# H05R00.net
KiCad netlist of a schematic drawn in EAGLE
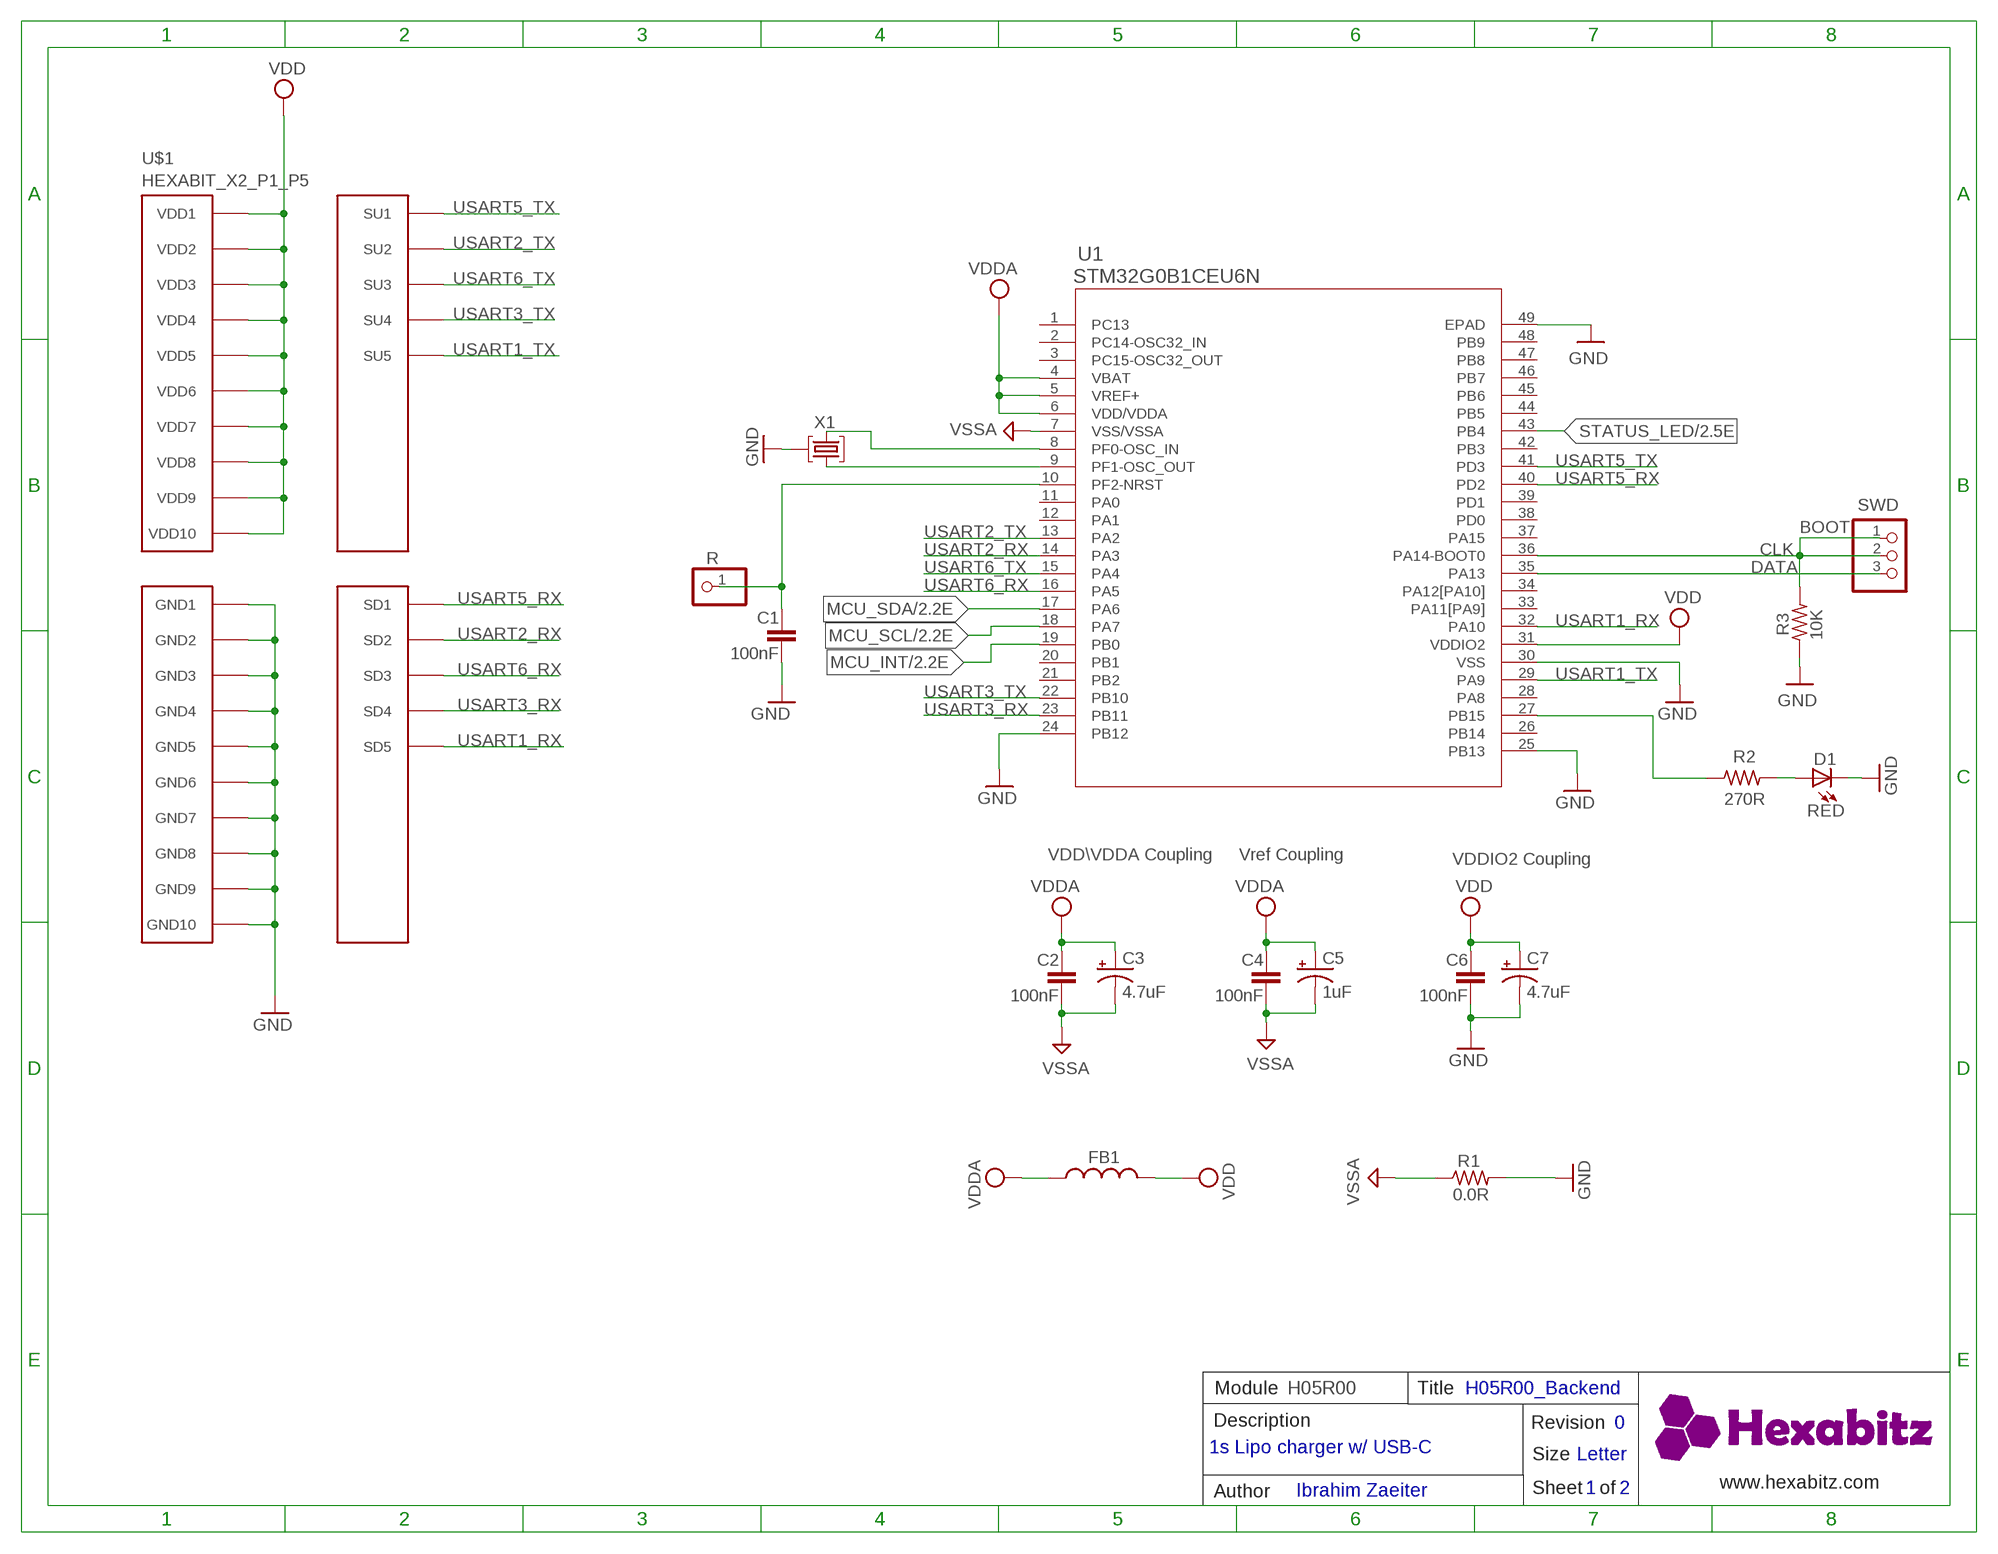
[diagram p0: schematic, sheet 1]
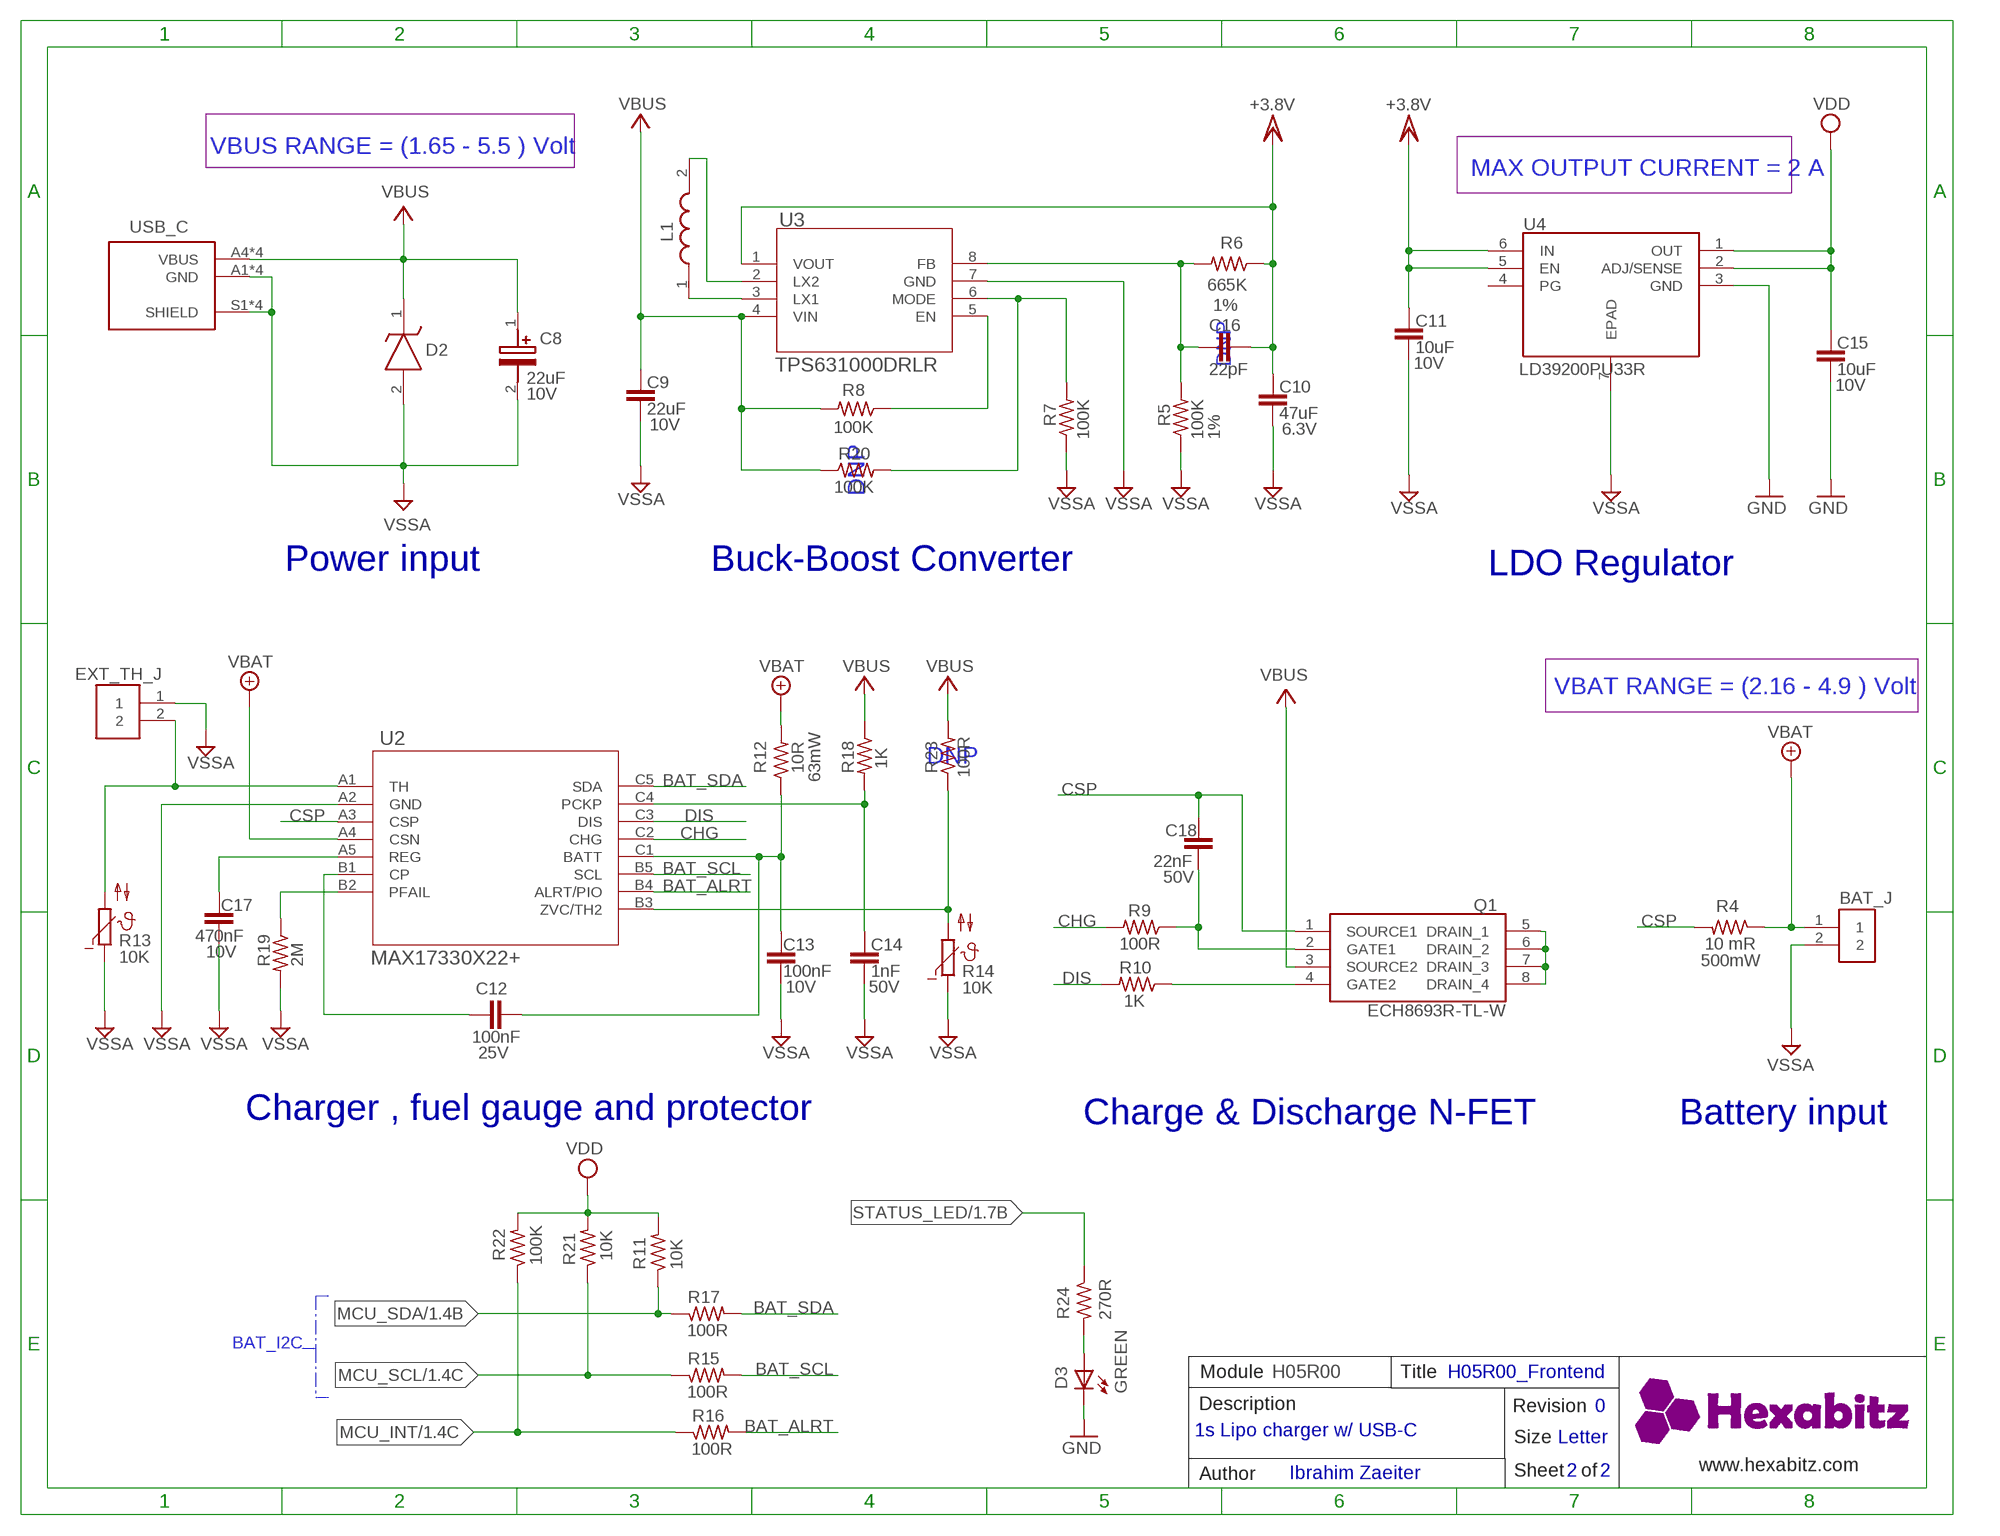
[diagram p1: schematic, sheet 2]

(export (version "E")
  (design (tool "Eeschema 10.0.6"))
  (components
    (comp (ref "BAT_J")
      (value "B2B-PH-K-S(LF)(SN)")
      (footprint "eagle-import:JST_B2B-PH-K-S(LF)(SN)")
      (fields (field (name "MF") "JST Sales"))
      (libsource (lib "eagle-import") (part "B2B-PH-K-S(LF)(SN)"))
    )
    (comp (ref "C8")
      (value "22uF")
      (footprint "eagle-import:T491B")
      (fields
        (field (name "MANUFACTURER_PART_NUMBER") "T491B226K010AT")
        (field (name "MOUSER_PART_NUMBER") "80-T491B226K010")
        (field (name "VOLTAGE") "10V")
      )
      (libsource (lib "eagle-import") (part "T491B226K010AT"))
    )
    (comp (ref "C9")
      (value "22uF")
      (footprint "eagle-import:C-0603")
      (fields (field (name "MPN") "GRM187R61A226ME15") (field (name "VOLTAGE_RATING") "10V"))
      (libsource (lib "eagle-import") (part "C-0603"))
    )
    (comp (ref "C10")
      (value "47uF")
      (footprint "eagle-import:C-0603")
      (fields (field (name "MPN") "CL10A476MQ8QRN") (field (name "VOLTAGE_RATING") "6.3V"))
      (libsource (lib "eagle-import") (part "C-0603"))
    )
    (comp (ref "C11")
      (value "10uF")
      (footprint "eagle-import:C-0603")
      (fields (field (name "MPN") "GRM187R61A226ME15") (field (name "VOLTAGE_RATING") "10V"))
      (libsource (lib "eagle-import") (part "C-0603"))
    )
    (comp (ref "C12")
      (value "100nF")
      (footprint "eagle-import:C-0603")
      (fields (field (name "VOLTAGE_RATING") "25V"))
      (libsource (lib "eagle-import") (part "C-0603"))
    )
    (comp (ref "C13")
      (value "100nF")
      (footprint "eagle-import:C-0603")
      (fields (field (name "VOLTAGE_RATING") "10V"))
      (libsource (lib "eagle-import") (part "C-0603"))
    )
    (comp (ref "C14")
      (value "1nF")
      (footprint "eagle-import:C-0603")
      (fields (field (name "VOLTAGE_RATING") "50V"))
      (libsource (lib "eagle-import") (part "C-0603"))
    )
    (comp (ref "C15")
      (value "10uF")
      (footprint "eagle-import:C-0603")
      (fields (field (name "MPN") "GRM187R61A226ME15") (field (name "VOLTAGE_RATING") "10V"))
      (libsource (lib "eagle-import") (part "C-0603"))
    )
    (comp (ref "C16")
      (value "22pF")
      (footprint "eagle-import:C-0603")
      (fields (field (name "STATE") "DNP"))
      (libsource (lib "eagle-import") (part "C-0603"))
    )
    (comp (ref "C17")
      (value "470nF")
      (footprint "eagle-import:C-0603")
      (fields (field (name "VOLTAGE_RATING") "10V"))
      (libsource (lib "eagle-import") (part "C-0603"))
    )
    (comp (ref "C18")
      (value "22nF")
      (footprint "eagle-import:C-0603")
      (fields (field (name "VOLTAGE_RATING") "50V"))
      (libsource (lib "eagle-import") (part "C-0603"))
    )
    (comp (ref "D2")
      (value "UCLAMP0501H.TCT")
      (footprint "eagle-import:SODFL1608X70N")
      (fields (field (name "MOUSER_PART_NUMBER") "947-UCLAMP0501H.TCT"))
      (libsource (lib "eagle-import") (part "UCLAMP0501H.TCT"))
    )
    (comp (ref "D3")
      (value "GREEN")
      (footprint "eagle-import:VLMS1300-GS08")
      (fields
        (field (name "MPN") "VLMS1300-GS08")
        (field (name "MFN") "Vishay")
        (field (name "MPN_1") "VLMS1300-GS08")
        (field (name "OCTOPART_URL") "https://octopart.com/vlms1300-gs08-vishay-21709201?r=sp&s=_gcP4_q8T1SC6PJQPTQ9yA")
      )
      (libsource (lib "eagle-import") (part "VLMS1300-GS08"))
    )
    (comp (ref "EXT_TH_J")
      (value "3-644456-2")
      (footprint "eagle-import:TE_3-644456-2")
      (fields (field (name "MF") "TE Connectivity") (field (name "MPN") "87224-1"))
      (libsource (lib "eagle-import") (part "3-644456-2"))
    )
    (comp (ref "L1")
      (value "DFE252012P-1R0M=P2")
      (footprint "eagle-import:DFE2HCAH1R0MJ0L")
      (fields (field (name "MOUSER_PART_NUMBER") "81-DFE252012P-1R0MP2"))
      (libsource (lib "eagle-import") (part "DFE252012P-1R0M=P2"))
    )
    (comp (ref "Q1")
      (value "ECH8693R-TL-W")
      (footprint "eagle-import:SOTFL65P280X95-8N")
      (fields (field (name "MOUSER_PART_NUMBER") "863-ECH8693R-TL-W"))
      (libsource (lib "eagle-import") (part "ECH8693R-TL-W"))
    )
    (comp (ref "R4")
      (value "10 mR")
      (footprint "eagle-import:R-0805")
      (fields (field (name "POWR") "500mW"))
      (libsource (lib "eagle-import") (part "R-0805"))
    )
    (comp (ref "R5")
      (value "100K")
      (footprint "eagle-import:R-0603")
      (fields (field (name "TOLERANCE") "1%"))
      (libsource (lib "eagle-import") (part "R-0603"))
    )
    (comp (ref "R6")
      (value "665K")
      (footprint "eagle-import:R-0603")
      (fields (field (name "TOLERANCE") "1%"))
      (libsource (lib "eagle-import") (part "R-0603"))
    )
    (comp (ref "R7")
      (value "100K")
      (footprint "eagle-import:R-0603")
      (libsource (lib "eagle-import") (part "R-0603"))
    )
    (comp (ref "R8")
      (value "100K")
      (footprint "eagle-import:R-0603")
      (libsource (lib "eagle-import") (part "R-0603"))
    )
    (comp (ref "R9")
      (value "100R")
      (footprint "eagle-import:R-0603")
      (libsource (lib "eagle-import") (part "R-0603"))
    )
    (comp (ref "R10")
      (value "1K")
      (footprint "eagle-import:R-0603")
      (libsource (lib "eagle-import") (part "R-0603"))
    )
    (comp (ref "R11")
      (value "10K")
      (footprint "eagle-import:R-0603")
      (libsource (lib "eagle-import") (part "R-0603"))
    )
    (comp (ref "R12")
      (value "10R")
      (footprint "eagle-import:R-0603")
      (fields (field (name "POWER") "63mW"))
      (libsource (lib "eagle-import") (part "R-0603"))
    )
    (comp (ref "R13")
      (value "10K")
      (footprint "eagle-import:R-0603")
      (fields (field (name "MPN") "NCP18XH103F03RB"))
      (libsource (lib "eagle-import") (part "NCP18XH103F03RBNCP18XH103F03RB"))
    )
    (comp (ref "R14")
      (value "10K")
      (footprint "eagle-import:R-0603")
      (fields (field (name "MPN") "NCP18XH103F03RB"))
      (libsource (lib "eagle-import") (part "NCP18XH103F03RBNCP18XH103F03RB"))
    )
    (comp (ref "R15")
      (value "100R")
      (footprint "eagle-import:R-0603")
      (libsource (lib "eagle-import") (part "R-0603"))
    )
    (comp (ref "R16")
      (value "100R")
      (footprint "eagle-import:R-0603")
      (libsource (lib "eagle-import") (part "R-0603"))
    )
    (comp (ref "R17")
      (value "100R")
      (footprint "eagle-import:R-0603")
      (libsource (lib "eagle-import") (part "R-0603"))
    )
    (comp (ref "R18")
      (value "1K")
      (footprint "eagle-import:R-0603")
      (libsource (lib "eagle-import") (part "R-0603"))
    )
    (comp (ref "R19")
      (value "2M")
      (footprint "eagle-import:R-0603")
      (libsource (lib "eagle-import") (part "R-0603"))
    )
    (comp (ref "R20")
      (value "100K")
      (footprint "eagle-import:R-0603")
      (fields (field (name "STATE") "DNP"))
      (libsource (lib "eagle-import") (part "R-0603"))
    )
    (comp (ref "R21")
      (value "10K")
      (footprint "eagle-import:R-0603")
      (libsource (lib "eagle-import") (part "R-0603"))
    )
    (comp (ref "R22")
      (value "100K")
      (footprint "eagle-import:R-0603")
      (libsource (lib "eagle-import") (part "R-0603"))
    )
    (comp (ref "R23")
      (value "DNP")
      (footprint "eagle-import:R-0603")
      (fields (field (name "RESISTANCE") "100R") (field (name "STATE") "DNP"))
      (libsource (lib "eagle-import") (part "R-0603"))
    )
    (comp (ref "R24")
      (value "270R")
      (footprint "eagle-import:R-0603")
      (libsource (lib "eagle-import") (part "R-0603"))
    )
    (comp (ref "U2")
      (value "MAX17330X22+")
      (footprint "eagle-import:21-100433_W151J2+1_MXM")
      (fields (field (name "COPYRIGHT") "Copyright (C) 2023 Ultra Librarian. All rights reserved."))
      (libsource (lib "eagle-import") (part "MAX17330X22+21-100433_W151J2+1_MXM"))
    )
    (comp (ref "U3")
      (value "TPS631000DRLR")
      (footprint "eagle-import:TPS631000DRLR_TEX")
      (fields (field (name "COPYRIGHT") "Copyright (C) 2023 Ultra Librarian. All rights reserved."))
      (libsource (lib "eagle-import") (part "TPS631000DRLRTPS631000DRLR_TEX"))
    )
    (comp (ref "U4")
      (value "LD39200PU33R")
      (footprint "eagle-import:SON95P300X300X100-7N")
      (fields (field (name "MOUSER_PART_NUMBER") "511-LD39200PU33R"))
      (libsource (lib "eagle-import") (part "LD39200PU33R"))
    )
    (comp (ref "USB_C")
      (value "UJC-HP-G-SMT-TR")
      (footprint "eagle-import:CUI_UJC-HP-G-SMT-TR")
      (fields (field (name "MF") "CUI Devices"))
      (libsource (lib "eagle-import") (part "UJC-HP-G-SMT-TR"))
    )
    (comp (ref "C1")
      (value "100nF")
      (footprint "eagle-import:C-0603")
      (libsource (lib "eagle-import") (part "C-0603"))
    )
    (comp (ref "C2")
      (value "100nF")
      (footprint "eagle-import:C-0603")
      (libsource (lib "eagle-import") (part "C-0603"))
    )
    (comp (ref "C3")
      (value "4.7uF")
      (footprint "eagle-import:C-0805-POL")
      (libsource (lib "eagle-import") (part "C-0805-POL"))
    )
    (comp (ref "C4")
      (value "100nF")
      (footprint "eagle-import:C-0603")
      (libsource (lib "eagle-import") (part "C-0603"))
    )
    (comp (ref "C5")
      (value "1uF")
      (footprint "eagle-import:C-0805-POL")
      (libsource (lib "eagle-import") (part "C-0805-POL"))
    )
    (comp (ref "C6")
      (value "100nF")
      (footprint "eagle-import:C-0603")
      (libsource (lib "eagle-import") (part "C-0603"))
    )
    (comp (ref "C7")
      (value "4.7uF")
      (footprint "eagle-import:C-0805-POL")
      (libsource (lib "eagle-import") (part "C-0805-POL"))
    )
    (comp (ref "D1")
      (value "RED")
      (footprint "eagle-import:VLMS1300-GS08")
      (fields
        (field (name "MPN") "VLMS1300-GS08")
        (field (name "MFN") "Vishay")
        (field (name "MPN_1") "VLMS1300-GS08")
        (field (name "OCTOPART_URL") "https://octopart.com/vlms1300-gs08-vishay-21709201?r=sp&s=_gcP4_q8T1SC6PJQPTQ9yA")
      )
      (libsource (lib "eagle-import") (part "VLMS1300-GS08"))
    )
    (comp (ref "FB1")
      (value "FB-0603")
      (footprint "eagle-import:FB-0603")
      (libsource (lib "eagle-import") (part "FB-0603"))
    )
    (comp (ref "R")
      (value "R")
      (footprint "eagle-import:1X01")
      (fields (field (name "MPN") "87227-1"))
      (libsource (lib "eagle-import") (part "PINHD-1X1"))
    )
    (comp (ref "R1")
      (value "0.0R")
      (footprint "eagle-import:R-0603")
      (libsource (lib "eagle-import") (part "R-0603"))
    )
    (comp (ref "R2")
      (value "270R")
      (footprint "eagle-import:R-0603")
      (libsource (lib "eagle-import") (part "R-0603"))
    )
    (comp (ref "R3")
      (value "10K")
      (footprint "eagle-import:R-0603")
      (libsource (lib "eagle-import") (part "R-0603"))
    )
    (comp (ref "SWD")
      (value "PINHD-1X3")
      (footprint "eagle-import:1X03")
      (libsource (lib "eagle-import") (part "PINHD-1X3"))
    )
    (comp (ref "U$1")
      (value "HEXABIT_X2_P1_P5")
      (footprint "eagle-import:HEXABIT_17.32_X2_P1_P5")
      (libsource (lib "eagle-import") (part "HEXABIT_X2_P1_P5"))
    )
    (comp (ref "U1")
      (value "STM32G0B1CEU6N")
      (footprint "eagle-import:HEXABITZ_ICS_QFN_B1CEU6_STM-L")
      (libsource (lib "eagle-import") (part "STM32G0B1CEU6N"))
    )
    (comp (ref "X1")
      (value "XTALL_CSTCE8M00G52")
      (footprint "eagle-import:XTALL_CSTCE8M00G52")
      (fields (field (name "MPN") "CSTCE8M00G52Z-R0"))
      (libsource (lib "eagle-import") (part "XTALL_CSTCE8M00G52"))
    )
  )
  (nets
    (net (code "1") (name "+3.8V") (class "Default")
      (node (ref "C10") (pin "2") (pinfunction "2_2") (pintype "passive"))
      (node (ref "C11") (pin "2") (pinfunction "2_2") (pintype "passive"))
      (node (ref "C16") (pin "1") (pinfunction "1_1") (pintype "passive"))
      (node (ref "R6") (pin "1") (pinfunction "1_1") (pintype "passive"))
      (node (ref "U3") (pin "1") (pinfunction "VOUT_1") (pintype "power_in"))
      (node (ref "U4") (pin "5") (pinfunction "EN_5") (pintype "bidirectional"))
      (node (ref "U4") (pin "6") (pinfunction "IN_6") (pintype "bidirectional"))
    )
    (net (code "2") (name "BAT_ALRT") (class "Default")
      (node (ref "R16") (pin "2") (pinfunction "2_2") (pintype "passive"))
      (node (ref "U2") (pin "B4") (pinfunction "ALRT/PIO_B4") (pintype "output"))
    )
    (net (code "3") (name "BAT_SCL") (class "Default")
      (node (ref "R15") (pin "2") (pinfunction "2_2") (pintype "passive"))
      (node (ref "U2") (pin "B5") (pinfunction "SCL_B5") (pintype "input"))
    )
    (net (code "4") (name "BAT_SDA") (class "Default")
      (node (ref "R17") (pin "2") (pinfunction "2_2") (pintype "passive"))
      (node (ref "U2") (pin "C5") (pinfunction "SDA_C5") (pintype "bidirectional"))
    )
    (net (code "5") (name "CHG") (class "Default")
      (node (ref "R9") (pin "2") (pinfunction "2_2") (pintype "passive"))
      (node (ref "U2") (pin "C2") (pinfunction "CHG_C2") (pintype "passive"))
    )
    (net (code "6") (name "CLK") (class "Default")
      (node (ref "R3") (pin "2") (pinfunction "2_2") (pintype "passive"))
      (node (ref "SWD") (pin "1") (pinfunction "1_1") (pintype "passive"))
      (node (ref "SWD") (pin "2") (pinfunction "2_2") (pintype "passive"))
      (node (ref "U1") (pin "36") (pinfunction "PA14-BOOT0_36") (pintype "bidirectional"))
    )
    (net (code "7") (name "CSP") (class "Default")
      (node (ref "C18") (pin "1") (pinfunction "1_1") (pintype "passive"))
      (node (ref "Q1") (pin "1") (pinfunction "SOURCE1_1") (pintype "bidirectional"))
      (node (ref "R4") (pin "2") (pinfunction "2_2") (pintype "passive"))
      (node (ref "U2") (pin "A3") (pinfunction "CSP_A3") (pintype "input"))
    )
    (net (code "8") (name "DATA") (class "Default")
      (node (ref "SWD") (pin "3") (pinfunction "3_3") (pintype "passive"))
      (node (ref "U1") (pin "35") (pinfunction "PA13_35") (pintype "bidirectional"))
    )
    (net (code "9") (name "DIS") (class "Default")
      (node (ref "R10") (pin "2") (pinfunction "2_2") (pintype "passive"))
      (node (ref "U2") (pin "C3") (pinfunction "DIS_C3") (pintype "passive"))
    )
    (net (code "10") (name "GND") (class "Default")
      (node (ref "C1") (pin "2") (pinfunction "2_2") (pintype "passive"))
      (node (ref "C15") (pin "1") (pinfunction "1_1") (pintype "passive"))
      (node (ref "C6") (pin "2") (pinfunction "2_2") (pintype "passive"))
      (node (ref "C7") (pin "2") (pinfunction "-_2") (pintype "passive"))
      (node (ref "D1") (pin "C") (pinfunction "C_C") (pintype "passive"))
      (node (ref "D3") (pin "C") (pinfunction "C_C") (pintype "passive"))
      (node (ref "R1") (pin "2") (pinfunction "2_2") (pintype "passive"))
      (node (ref "R3") (pin "1") (pinfunction "1_1") (pintype "passive"))
      (node (ref "U$1") (pin "PAD_PD11") (pinfunction "GND1_PAD_PD11") (pintype "power_in"))
      (node (ref "U$1") (pin "PAD_PD12") (pinfunction "GND2_PAD_PD12") (pintype "power_in"))
      (node (ref "U$1") (pin "PAD_PD13") (pinfunction "GND3_PAD_PD13") (pintype "power_in"))
      (node (ref "U$1") (pin "PAD_PD14") (pinfunction "GND4_PAD_PD14") (pintype "power_in"))
      (node (ref "U$1") (pin "PAD_PD15") (pinfunction "GND5_PAD_PD15") (pintype "power_in"))
      (node (ref "U$1") (pin "PAD_PD16") (pinfunction "GND6_PAD_PD16") (pintype "power_in"))
      (node (ref "U$1") (pin "PAD_PD17") (pinfunction "GND7_PAD_PD17") (pintype "power_in"))
      (node (ref "U$1") (pin "PAD_PD18") (pinfunction "GND8_PAD_PD18") (pintype "power_in"))
      (node (ref "U$1") (pin "PAD_PD19") (pinfunction "GND9_PAD_PD19") (pintype "power_in"))
      (node (ref "U$1") (pin "PAD_PD20") (pinfunction "GND10_PAD_PD20") (pintype "power_in"))
      (node (ref "U1") (pin "24") (pinfunction "PB12_24") (pintype "bidirectional"))
      (node (ref "U1") (pin "25") (pinfunction "PB13_25") (pintype "bidirectional"))
      (node (ref "U1") (pin "30") (pinfunction "VSS_30") (pintype "passive"))
      (node (ref "U1") (pin "49") (pinfunction "EPAD_49") (pintype "passive"))
      (node (ref "U4") (pin "3") (pinfunction "GND_3") (pintype "bidirectional"))
      (node (ref "X1") (pin "P$2") (pinfunction "2_P$2") (pintype "passive"))
    )
    (net (code "11") (name "MCU_INT") (class "Default")
      (node (ref "R16") (pin "1") (pinfunction "1_1") (pintype "passive"))
      (node (ref "R22") (pin "1") (pinfunction "1_1") (pintype "passive"))
      (node (ref "U1") (pin "19") (pinfunction "PB0_19") (pintype "bidirectional"))
    )
    (net (code "12") (name "MCU_SCL") (class "Default")
      (node (ref "R15") (pin "1") (pinfunction "1_1") (pintype "passive"))
      (node (ref "R21") (pin "1") (pinfunction "1_1") (pintype "passive"))
      (node (ref "U1") (pin "18") (pinfunction "PA7_18") (pintype "bidirectional"))
    )
    (net (code "13") (name "MCU_SDA") (class "Default")
      (node (ref "R11") (pin "1") (pinfunction "1_1") (pintype "passive"))
      (node (ref "R17") (pin "1") (pinfunction "1_1") (pintype "passive"))
      (node (ref "U1") (pin "17") (pinfunction "PA6_17") (pintype "bidirectional"))
    )
    (net (code "14") (name "Net-(D1-PadA)") (class "Default")
      (node (ref "D1") (pin "A") (pinfunction "A_A") (pintype "passive"))
      (node (ref "R2") (pin "2") (pinfunction "2_2") (pintype "passive"))
    )
    (net (code "15") (name "Net-(D3-PadA)") (class "Default")
      (node (ref "D3") (pin "A") (pinfunction "A_A") (pintype "passive"))
      (node (ref "R24") (pin "2") (pinfunction "2_2") (pintype "passive"))
    )
    (net (code "16") (name "Net-(Q1-DRAIN_1)") (class "Default")
      (node (ref "Q1") (pin "5") (pinfunction "DRAIN_1_5") (pintype "bidirectional"))
      (node (ref "Q1") (pin "6") (pinfunction "DRAIN_2_6") (pintype "bidirectional"))
      (node (ref "Q1") (pin "7") (pinfunction "DRAIN_3_7") (pintype "bidirectional"))
      (node (ref "Q1") (pin "8") (pinfunction "DRAIN_4_8") (pintype "bidirectional"))
    )
    (net (code "17") (name "Net-(Q1-GATE1)") (class "Default")
      (node (ref "C18") (pin "2") (pinfunction "2_2") (pintype "passive"))
      (node (ref "Q1") (pin "2") (pinfunction "GATE1_2") (pintype "bidirectional"))
      (node (ref "R9") (pin "1") (pinfunction "1_1") (pintype "passive"))
    )
    (net (code "18") (name "Net-(Q1-GATE2)") (class "Default")
      (node (ref "Q1") (pin "4") (pinfunction "GATE2_4") (pintype "bidirectional"))
      (node (ref "R10") (pin "1") (pinfunction "1_1") (pintype "passive"))
    )
    (net (code "19") (name "Net-(U1-PB15)") (class "Default")
      (node (ref "R2") (pin "1") (pinfunction "1_1") (pintype "passive"))
      (node (ref "U1") (pin "27") (pinfunction "PB15_27") (pintype "bidirectional"))
    )
    (net (code "20") (name "Net-(U1-PF0-OSC_IN)") (class "Default")
      (node (ref "U1") (pin "8") (pinfunction "PF0-OSC_IN_8") (pintype "bidirectional"))
      (node (ref "X1") (pin "P$3") (pinfunction "3_P$3") (pintype "passive"))
    )
    (net (code "21") (name "Net-(U1-PF1-OSC_OUT)") (class "Default")
      (node (ref "U1") (pin "9") (pinfunction "PF1-OSC_OUT_9") (pintype "bidirectional"))
      (node (ref "X1") (pin "P$1") (pinfunction "1_P$1") (pintype "passive"))
    )
    (net (code "22") (name "Net-(U1-PF2-NRST)") (class "Default")
      (node (ref "C1") (pin "1") (pinfunction "1_1") (pintype "passive"))
      (node (ref "R") (pin "1") (pinfunction "1_1") (pintype "passive"))
      (node (ref "U1") (pin "10") (pinfunction "PF2-NRST_10") (pintype "bidirectional"))
    )
    (net (code "23") (name "Net-(U2-BATT)") (class "Default")
      (node (ref "C12") (pin "2") (pinfunction "2_2") (pintype "passive"))
      (node (ref "C13") (pin "1") (pinfunction "1_1") (pintype "passive"))
      (node (ref "R12") (pin "1") (pinfunction "1_1") (pintype "passive"))
      (node (ref "U2") (pin "C1") (pinfunction "BATT_C1") (pintype "power_in"))
    )
    (net (code "24") (name "Net-(U2-CP)") (class "Default")
      (node (ref "C12") (pin "1") (pinfunction "1_1") (pintype "passive"))
      (node (ref "U2") (pin "B1") (pinfunction "CP_B1") (pintype "output"))
    )
    (net (code "25") (name "Net-(U2-PCKP)") (class "Default")
      (node (ref "C14") (pin "1") (pinfunction "1_1") (pintype "passive"))
      (node (ref "R18") (pin "2") (pinfunction "2_2") (pintype "passive"))
      (node (ref "U2") (pin "C4") (pinfunction "PCKP_C4") (pintype "passive"))
    )
    (net (code "26") (name "Net-(U2-PFAIL)") (class "Default")
      (node (ref "R19") (pin "1") (pinfunction "1_1") (pintype "passive"))
      (node (ref "U2") (pin "B2") (pinfunction "PFAIL_B2") (pintype "passive"))
    )
    (net (code "27") (name "Net-(U2-REG)") (class "Default")
      (node (ref "C17") (pin "2") (pinfunction "2_2") (pintype "passive"))
      (node (ref "U2") (pin "A5") (pinfunction "REG_A5") (pintype "power_in"))
    )
    (net (code "28") (name "Net-(U2-TH)") (class "Default")
      (node (ref "EXT_TH_J") (pin "2") (pinfunction "2_2") (pintype "passive"))
      (node (ref "R13") (pin "2") (pinfunction "2_2") (pintype "passive"))
      (node (ref "U2") (pin "A1") (pinfunction "TH_A1") (pintype "passive"))
    )
    (net (code "29") (name "Net-(U2-ZVC{slash}TH2)") (class "Default")
      (node (ref "R14") (pin "2") (pinfunction "2_2") (pintype "passive"))
      (node (ref "R23") (pin "1") (pinfunction "1_1") (pintype "passive"))
      (node (ref "U2") (pin "B3") (pinfunction "ZVC/TH2_B3") (pintype "input"))
    )
    (net (code "30") (name "Net-(U3-EN)") (class "Default")
      (node (ref "R8") (pin "1") (pinfunction "1_1") (pintype "passive"))
      (node (ref "U3") (pin "5") (pinfunction "EN_5") (pintype "input"))
    )
    (net (code "31") (name "Net-(U3-FB)") (class "Default")
      (node (ref "C16") (pin "2") (pinfunction "2_2") (pintype "passive"))
      (node (ref "R5") (pin "2") (pinfunction "2_2") (pintype "passive"))
      (node (ref "R6") (pin "2") (pinfunction "2_2") (pintype "passive"))
      (node (ref "U3") (pin "8") (pinfunction "FB_8") (pintype "input"))
    )
    (net (code "32") (name "Net-(U3-LX1)") (class "Default")
      (node (ref "L1") (pin "1") (pinfunction "1_1") (pintype "bidirectional"))
      (node (ref "U3") (pin "3") (pinfunction "LX1_3") (pintype "power_in"))
    )
    (net (code "33") (name "Net-(U3-LX2)") (class "Default")
      (node (ref "L1") (pin "2") (pinfunction "2_2") (pintype "bidirectional"))
      (node (ref "U3") (pin "2") (pinfunction "LX2_2") (pintype "power_in"))
    )
    (net (code "34") (name "Net-(U3-MODE)") (class "Default")
      (node (ref "R20") (pin "2") (pinfunction "2_2") (pintype "passive"))
      (node (ref "R7") (pin "2") (pinfunction "2_2") (pintype "passive"))
      (node (ref "U3") (pin "6") (pinfunction "MODE_6") (pintype "input"))
    )
    (net (code "35") (name "STATUS_LED") (class "Default")
      (node (ref "R24") (pin "1") (pinfunction "1_1") (pintype "passive"))
      (node (ref "U1") (pin "43") (pinfunction "PB4_43") (pintype "bidirectional"))
    )
    (net (code "36") (name "USART1_RX") (class "Default")
      (node (ref "U$1") (pin "PAD_PD5") (pinfunction "SD5_PAD_PD5") (pintype "bidirectional"))
      (node (ref "U1") (pin "32") (pinfunction "PA10_32") (pintype "bidirectional"))
    )
    (net (code "37") (name "USART1_TX") (class "Default")
      (node (ref "U$1") (pin "PAD_PU5") (pinfunction "SU5_PAD_PU5") (pintype "bidirectional"))
      (node (ref "U1") (pin "29") (pinfunction "PA9_29") (pintype "bidirectional"))
    )
    (net (code "38") (name "USART2_RX") (class "Default")
      (node (ref "U$1") (pin "PAD_PD2") (pinfunction "SD2_PAD_PD2") (pintype "bidirectional"))
      (node (ref "U1") (pin "14") (pinfunction "PA3_14") (pintype "bidirectional"))
    )
    (net (code "39") (name "USART2_TX") (class "Default")
      (node (ref "U$1") (pin "PAD_PU2") (pinfunction "SU2_PAD_PU2") (pintype "bidirectional"))
      (node (ref "U1") (pin "13") (pinfunction "PA2_13") (pintype "bidirectional"))
    )
    (net (code "40") (name "USART3_RX") (class "Default")
      (node (ref "U$1") (pin "PAD_PD4") (pinfunction "SD4_PAD_PD4") (pintype "bidirectional"))
      (node (ref "U1") (pin "23") (pinfunction "PB11_23") (pintype "bidirectional"))
    )
    (net (code "41") (name "USART3_TX") (class "Default")
      (node (ref "U$1") (pin "PAD_PU4") (pinfunction "SU4_PAD_PU4") (pintype "bidirectional"))
      (node (ref "U1") (pin "22") (pinfunction "PB10_22") (pintype "bidirectional"))
    )
    (net (code "42") (name "USART5_RX") (class "Default")
      (node (ref "U$1") (pin "PAD_PD1") (pinfunction "SD1_PAD_PD1") (pintype "bidirectional"))
      (node (ref "U1") (pin "40") (pinfunction "PD2_40") (pintype "bidirectional"))
    )
    (net (code "43") (name "USART5_TX") (class "Default")
      (node (ref "U$1") (pin "PAD_PU1") (pinfunction "SU1_PAD_PU1") (pintype "bidirectional"))
      (node (ref "U1") (pin "41") (pinfunction "PD3_41") (pintype "bidirectional"))
    )
    (net (code "44") (name "USART6_RX") (class "Default")
      (node (ref "U$1") (pin "PAD_PD3") (pinfunction "SD3_PAD_PD3") (pintype "bidirectional"))
      (node (ref "U1") (pin "16") (pinfunction "PA5_16") (pintype "bidirectional"))
    )
    (net (code "45") (name "USART6_TX") (class "Default")
      (node (ref "U$1") (pin "PAD_PU3") (pinfunction "SU3_PAD_PU3") (pintype "bidirectional"))
      (node (ref "U1") (pin "15") (pinfunction "PA4_15") (pintype "bidirectional"))
    )
    (net (code "46") (name "VBAT") (class "Default")
      (node (ref "BAT_J") (pin "1") (pinfunction "1_1") (pintype "passive"))
      (node (ref "R12") (pin "2") (pinfunction "2_2") (pintype "passive"))
      (node (ref "R4") (pin "1") (pinfunction "1_1") (pintype "passive"))
      (node (ref "U2") (pin "A4") (pinfunction "CSN_A4") (pintype "input"))
    )
    (net (code "47") (name "VBUS") (class "Default")
      (node (ref "C8") (pin "1") (pinfunction "+_1") (pintype "bidirectional"))
      (node (ref "C9") (pin "2") (pinfunction "2_2") (pintype "passive"))
      (node (ref "D2") (pin "1") (pinfunction "K_1") (pintype "bidirectional"))
      (node (ref "Q1") (pin "3") (pinfunction "SOURCE2_3") (pintype "bidirectional"))
      (node (ref "R18") (pin "1") (pinfunction "1_1") (pintype "passive"))
      (node (ref "R20") (pin "1") (pinfunction "1_1") (pintype "passive"))
      (node (ref "R23") (pin "2") (pinfunction "2_2") (pintype "passive"))
      (node (ref "R8") (pin "2") (pinfunction "2_2") (pintype "passive"))
      (node (ref "U3") (pin "4") (pinfunction "VIN_4") (pintype "power_in"))
      (node (ref "USB_C") (pin "A4") (pinfunction "VBUS_A4") (pintype "power_in"))
      (node (ref "USB_C") (pin "A9") (pinfunction "VBUS_A9") (pintype "power_in"))
      (node (ref "USB_C") (pin "B4") (pinfunction "VBUS_B4") (pintype "power_in"))
      (node (ref "USB_C") (pin "B9") (pinfunction "VBUS_B9") (pintype "power_in"))
    )
    (net (code "48") (name "VDD") (class "Default")
      (node (ref "C15") (pin "2") (pinfunction "2_2") (pintype "passive"))
      (node (ref "C6") (pin "1") (pinfunction "1_1") (pintype "passive"))
      (node (ref "C7") (pin "1") (pinfunction "+_1") (pintype "passive"))
      (node (ref "FB1") (pin "2") (pinfunction "2_2") (pintype "passive"))
      (node (ref "R11") (pin "2") (pinfunction "2_2") (pintype "passive"))
      (node (ref "R21") (pin "2") (pinfunction "2_2") (pintype "passive"))
      (node (ref "R22") (pin "2") (pinfunction "2_2") (pintype "passive"))
      (node (ref "U$1") (pin "PAD_PU11") (pinfunction "VDD1_PAD_PU11") (pintype "power_in"))
      (node (ref "U$1") (pin "PAD_PU12") (pinfunction "VDD2_PAD_PU12") (pintype "power_in"))
      (node (ref "U$1") (pin "PAD_PU13") (pinfunction "VDD3_PAD_PU13") (pintype "power_in"))
      (node (ref "U$1") (pin "PAD_PU14") (pinfunction "VDD4_PAD_PU14") (pintype "power_in"))
      (node (ref "U$1") (pin "PAD_PU15") (pinfunction "VDD5_PAD_PU15") (pintype "power_in"))
      (node (ref "U$1") (pin "PAD_PU16") (pinfunction "VDD6_PAD_PU16") (pintype "power_in"))
      (node (ref "U$1") (pin "PAD_PU17") (pinfunction "VDD7_PAD_PU17") (pintype "power_in"))
      (node (ref "U$1") (pin "PAD_PU18") (pinfunction "VDD8_PAD_PU18") (pintype "power_in"))
      (node (ref "U$1") (pin "PAD_PU19") (pinfunction "VDD9_PAD_PU19") (pintype "power_in"))
      (node (ref "U$1") (pin "PAD_PU20") (pinfunction "VDD10_PAD_PU20") (pintype "power_in"))
      (node (ref "U1") (pin "31") (pinfunction "VDDIO2_31") (pintype "power_in"))
      (node (ref "U4") (pin "1") (pinfunction "OUT_1") (pintype "bidirectional"))
      (node (ref "U4") (pin "2") (pinfunction "ADJ/SENSE_2") (pintype "bidirectional"))
    )
    (net (code "49") (name "VDDA") (class "Default")
      (node (ref "C2") (pin "1") (pinfunction "1_1") (pintype "passive"))
      (node (ref "C3") (pin "1") (pinfunction "+_1") (pintype "passive"))
      (node (ref "C4") (pin "1") (pinfunction "1_1") (pintype "passive"))
      (node (ref "C5") (pin "1") (pinfunction "+_1") (pintype "passive"))
      (node (ref "FB1") (pin "1") (pinfunction "1_1") (pintype "passive"))
      (node (ref "U1") (pin "4") (pinfunction "VBAT_4") (pintype "power_in"))
      (node (ref "U1") (pin "5") (pinfunction "VREF+_5") (pintype "power_in"))
      (node (ref "U1") (pin "6") (pinfunction "VDD/VDDA_6") (pintype "power_in"))
    )
    (net (code "50") (name "VSSA") (class "Default")
      (node (ref "BAT_J") (pin "2") (pinfunction "2_2") (pintype "passive"))
      (node (ref "C10") (pin "1") (pinfunction "1_1") (pintype "passive"))
      (node (ref "C11") (pin "1") (pinfunction "1_1") (pintype "passive"))
      (node (ref "C13") (pin "2") (pinfunction "2_2") (pintype "passive"))
      (node (ref "C14") (pin "2") (pinfunction "2_2") (pintype "passive"))
      (node (ref "C17") (pin "1") (pinfunction "1_1") (pintype "passive"))
      (node (ref "C2") (pin "2") (pinfunction "2_2") (pintype "passive"))
      (node (ref "C3") (pin "2") (pinfunction "-_2") (pintype "passive"))
      (node (ref "C4") (pin "2") (pinfunction "2_2") (pintype "passive"))
      (node (ref "C5") (pin "2") (pinfunction "-_2") (pintype "passive"))
      (node (ref "C8") (pin "2") (pinfunction "-_2") (pintype "bidirectional"))
      (node (ref "C9") (pin "1") (pinfunction "1_1") (pintype "passive"))
      (node (ref "D2") (pin "2") (pinfunction "A_2") (pintype "bidirectional"))
      (node (ref "EXT_TH_J") (pin "1") (pinfunction "1_1") (pintype "passive"))
      (node (ref "R1") (pin "1") (pinfunction "1_1") (pintype "passive"))
      (node (ref "R13") (pin "1") (pinfunction "1_1") (pintype "passive"))
      (node (ref "R14") (pin "1") (pinfunction "1_1") (pintype "passive"))
      (node (ref "R19") (pin "2") (pinfunction "2_2") (pintype "passive"))
      (node (ref "R5") (pin "1") (pinfunction "1_1") (pintype "passive"))
      (node (ref "R7") (pin "1") (pinfunction "1_1") (pintype "passive"))
      (node (ref "U1") (pin "7") (pinfunction "VSS/VSSA_7") (pintype "passive"))
      (node (ref "U2") (pin "A2") (pinfunction "GND_A2") (pintype "passive"))
      (node (ref "U3") (pin "7") (pinfunction "GND_7") (pintype "power_in"))
      (node (ref "U4") (pin "7") (pinfunction "EPAD_7") (pintype "bidirectional"))
      (node (ref "USB_C") (pin "A1") (pinfunction "GND_A1") (pintype "power_in"))
      (node (ref "USB_C") (pin "A12") (pinfunction "GND_A12") (pintype "power_in"))
      (node (ref "USB_C") (pin "B1") (pinfunction "GND_B1") (pintype "power_in"))
      (node (ref "USB_C") (pin "B12") (pinfunction "GND_B12") (pintype "power_in"))
      (node (ref "USB_C") (pin "S1") (pinfunction "SHIELD_S1") (pintype "passive"))
      (node (ref "USB_C") (pin "S2") (pinfunction "SHIELD_S2") (pintype "passive"))
      (node (ref "USB_C") (pin "S3") (pinfunction "SHIELD_S3") (pintype "passive"))
      (node (ref "USB_C") (pin "S4") (pinfunction "SHIELD_S4") (pintype "passive"))
    )
    (net (code "51") (name "unconnected-(U1-PA0-Pad11)") (class "Default")
      (node (ref "U1") (pin "11") (pinfunction "PA0_11") (pintype "bidirectional"))
    )
    (net (code "52") (name "unconnected-(U1-PA1-Pad12)") (class "Default")
      (node (ref "U1") (pin "12") (pinfunction "PA1_12") (pintype "bidirectional"))
    )
    (net (code "53") (name "unconnected-(U1-PA8-Pad28)") (class "Default")
      (node (ref "U1") (pin "28") (pinfunction "PA8_28") (pintype "bidirectional"))
    )
    (net (code "54") (name "unconnected-(U1-PA11[PA9]-Pad33)") (class "Default")
      (node (ref "U1") (pin "33") (pinfunction "PA11[PA9]_33") (pintype "bidirectional"))
    )
    (net (code "55") (name "unconnected-(U1-PA12[PA10]-Pad34)") (class "Default")
      (node (ref "U1") (pin "34") (pinfunction "PA12[PA10]_34") (pintype "bidirectional"))
    )
    (net (code "56") (name "unconnected-(U1-PA15-Pad37)") (class "Default")
      (node (ref "U1") (pin "37") (pinfunction "PA15_37") (pintype "bidirectional"))
    )
    (net (code "57") (name "unconnected-(U1-PB1-Pad20)") (class "Default")
      (node (ref "U1") (pin "20") (pinfunction "PB1_20") (pintype "bidirectional"))
    )
    (net (code "58") (name "unconnected-(U1-PB2-Pad21)") (class "Default")
      (node (ref "U1") (pin "21") (pinfunction "PB2_21") (pintype "bidirectional"))
    )
    (net (code "59") (name "unconnected-(U1-PB3-Pad42)") (class "Default")
      (node (ref "U1") (pin "42") (pinfunction "PB3_42") (pintype "bidirectional"))
    )
    (net (code "60") (name "unconnected-(U1-PB5-Pad44)") (class "Default")
      (node (ref "U1") (pin "44") (pinfunction "PB5_44") (pintype "bidirectional"))
    )
    (net (code "61") (name "unconnected-(U1-PB6-Pad45)") (class "Default")
      (node (ref "U1") (pin "45") (pinfunction "PB6_45") (pintype "bidirectional"))
    )
    (net (code "62") (name "unconnected-(U1-PB7-Pad46)") (class "Default")
      (node (ref "U1") (pin "46") (pinfunction "PB7_46") (pintype "bidirectional"))
    )
    (net (code "63") (name "unconnected-(U1-PB8-Pad47)") (class "Default")
      (node (ref "U1") (pin "47") (pinfunction "PB8_47") (pintype "bidirectional"))
    )
    (net (code "64") (name "unconnected-(U1-PB9-Pad48)") (class "Default")
      (node (ref "U1") (pin "48") (pinfunction "PB9_48") (pintype "bidirectional"))
    )
    (net (code "65") (name "unconnected-(U1-PB14-Pad26)") (class "Default")
      (node (ref "U1") (pin "26") (pinfunction "PB14_26") (pintype "bidirectional"))
    )
    (net (code "66") (name "unconnected-(U1-PC13-Pad1)") (class "Default")
      (node (ref "U1") (pin "1") (pinfunction "PC13_1") (pintype "bidirectional"))
    )
    (net (code "67") (name "unconnected-(U1-PC14-OSC32_IN-Pad2)") (class "Default")
      (node (ref "U1") (pin "2") (pinfunction "PC14-OSC32_IN_2") (pintype "bidirectional"))
    )
    (net (code "68") (name "unconnected-(U1-PC15-OSC32_OUT-Pad3)") (class "Default")
      (node (ref "U1") (pin "3") (pinfunction "PC15-OSC32_OUT_3") (pintype "bidirectional"))
    )
    (net (code "69") (name "unconnected-(U1-PD0-Pad38)") (class "Default")
      (node (ref "U1") (pin "38") (pinfunction "PD0_38") (pintype "bidirectional"))
    )
    (net (code "70") (name "unconnected-(U1-PD1-Pad39)") (class "Default")
      (node (ref "U1") (pin "39") (pinfunction "PD1_39") (pintype "bidirectional"))
    )
    (net (code "71") (name "unconnected-(U4-PG-Pad4)") (class "Default")
      (node (ref "U4") (pin "4") (pinfunction "PG_4") (pintype "bidirectional"))
    )
  )
)
